# RAM_Board_Deux.net
KiCad netlist of a schematic drawn in EAGLE
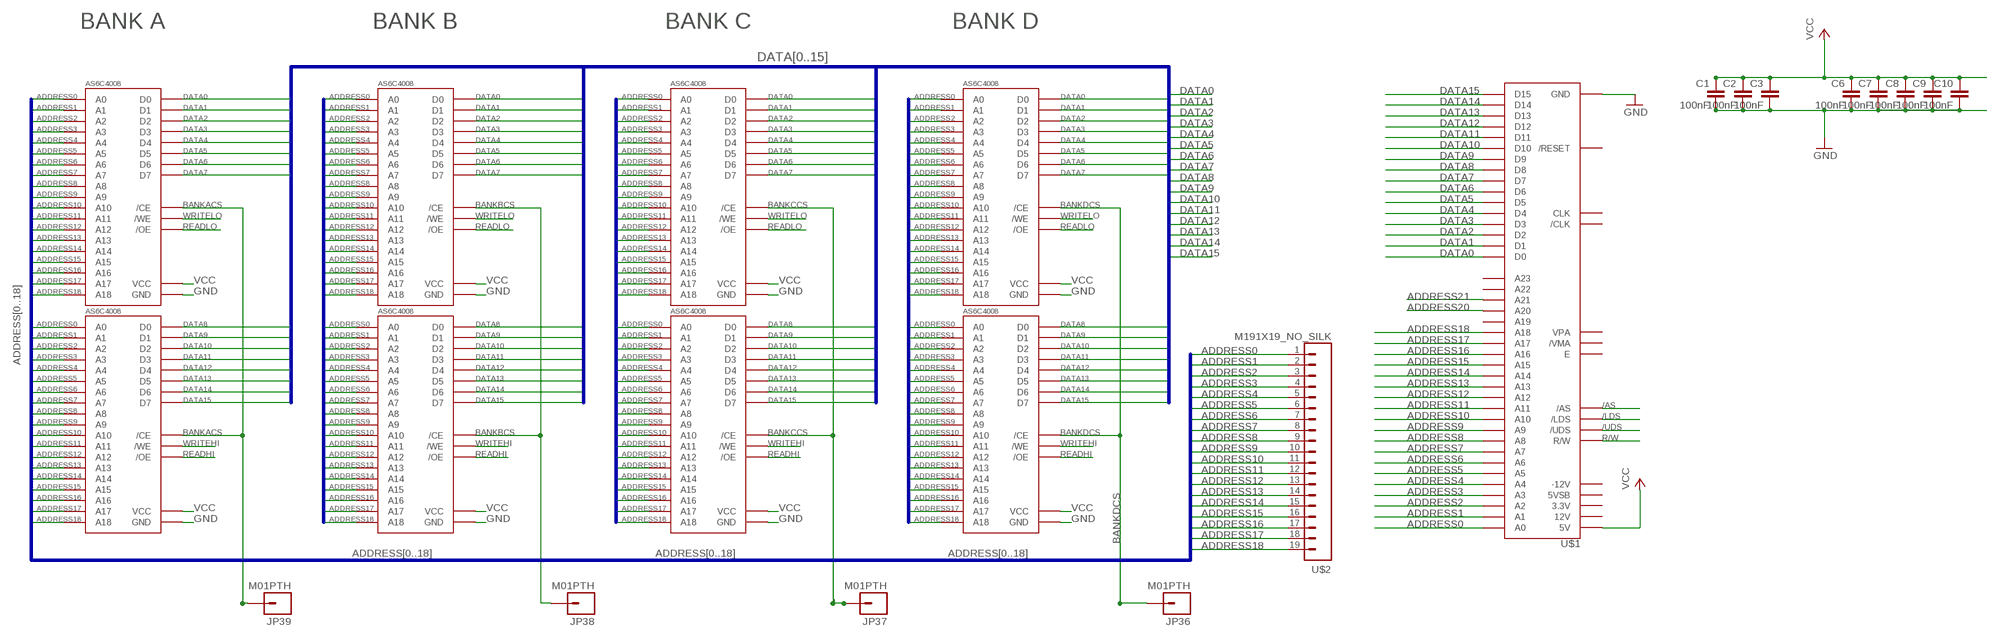
[diagram p0: schematic, sheet 1]

(export (version "E")
  (design (tool "Eeschema 10.0.6"))
  (components
    (comp (ref "C1")
      (value "100nF")
      (footprint "eagle-import:CAP-PTH-SMALL")
      (libsource (lib "eagle-import") (part "CAPPTH"))
    )
    (comp (ref "C2")
      (value "100nF")
      (footprint "eagle-import:CAP-PTH-SMALL")
      (libsource (lib "eagle-import") (part "CAPPTH"))
    )
    (comp (ref "C3")
      (value "100nF")
      (footprint "eagle-import:CAP-PTH-SMALL")
      (libsource (lib "eagle-import") (part "CAPPTH"))
    )
    (comp (ref "C6")
      (value "100nF")
      (footprint "eagle-import:CAP-PTH-SMALL")
      (libsource (lib "eagle-import") (part "CAPPTH"))
    )
    (comp (ref "C7")
      (value "100nF")
      (footprint "eagle-import:CAP-PTH-SMALL")
      (libsource (lib "eagle-import") (part "CAPPTH"))
    )
    (comp (ref "C8")
      (value "100nF")
      (footprint "eagle-import:CAP-PTH-SMALL")
      (libsource (lib "eagle-import") (part "CAPPTH"))
    )
    (comp (ref "C9")
      (value "100nF")
      (footprint "eagle-import:CAP-PTH-SMALL")
      (libsource (lib "eagle-import") (part "CAPPTH"))
    )
    (comp (ref "C10")
      (value "100nF")
      (footprint "eagle-import:CAP-PTH-SMALL")
      (libsource (lib "eagle-import") (part "CAPPTH"))
    )
    (comp (ref "JP36")
      (value "M01PTH")
      (footprint "eagle-import:1X01")
      (libsource (lib "eagle-import") (part "M01PTH"))
    )
    (comp (ref "JP37")
      (value "M01PTH")
      (footprint "eagle-import:1X01")
      (libsource (lib "eagle-import") (part "M01PTH"))
    )
    (comp (ref "JP38")
      (value "M01PTH")
      (footprint "eagle-import:1X01")
      (libsource (lib "eagle-import") (part "M01PTH"))
    )
    (comp (ref "JP39")
      (value "M01PTH")
      (footprint "eagle-import:1X01")
      (libsource (lib "eagle-import") (part "M01PTH"))
    )
    (comp (ref "U$1")
      (value "BLANKBOARD")
      (footprint "eagle-import:BLANKBOARD")
      (libsource (lib "eagle-import") (part "BLANKBOARD"))
    )
    (comp (ref "U$2")
      (value "M191X19_NO_SILK")
      (footprint "eagle-import:1X19_NO_SILK")
      (libsource (lib "eagle-import") (part "M191X19_NO_SILK"))
    )
    (comp (ref "U1")
      (value "AS6C4008")
      (footprint "eagle-import:DIL32")
      (libsource (lib "eagle-import") (part "AS6C4008"))
    )
    (comp (ref "U2")
      (value "AS6C4008")
      (footprint "eagle-import:DIL32")
      (libsource (lib "eagle-import") (part "AS6C4008"))
    )
    (comp (ref "U3")
      (value "AS6C4008")
      (footprint "eagle-import:DIL32")
      (libsource (lib "eagle-import") (part "AS6C4008"))
    )
    (comp (ref "U4")
      (value "AS6C4008")
      (footprint "eagle-import:DIL32")
      (libsource (lib "eagle-import") (part "AS6C4008"))
    )
    (comp (ref "U5")
      (value "AS6C4008")
      (footprint "eagle-import:DIL32")
      (libsource (lib "eagle-import") (part "AS6C4008"))
    )
    (comp (ref "U6")
      (value "AS6C4008")
      (footprint "eagle-import:DIL32")
      (libsource (lib "eagle-import") (part "AS6C4008"))
    )
    (comp (ref "U7")
      (value "AS6C4008")
      (footprint "eagle-import:DIL32")
      (libsource (lib "eagle-import") (part "AS6C4008"))
    )
    (comp (ref "U8")
      (value "AS6C4008")
      (footprint "eagle-import:DIL32")
      (libsource (lib "eagle-import") (part "AS6C4008"))
    )
  )
  (nets
    (net (code "3") (name "ADDRESS0") (class "Default")
      (node (ref "U$1") (pin "A0") (pinfunction "A0_A0") (pintype "bidirectional"))
      (node (ref "U$2") (pin "1") (pinfunction "1_1") (pintype "passive"))
      (node (ref "U1") (pin "12") (pinfunction "A0_12") (pintype "input"))
      (node (ref "U2") (pin "12") (pinfunction "A0_12") (pintype "input"))
      (node (ref "U3") (pin "12") (pinfunction "A0_12") (pintype "input"))
      (node (ref "U4") (pin "12") (pinfunction "A0_12") (pintype "input"))
      (node (ref "U5") (pin "12") (pinfunction "A0_12") (pintype "input"))
      (node (ref "U6") (pin "12") (pinfunction "A0_12") (pintype "input"))
      (node (ref "U7") (pin "12") (pinfunction "A0_12") (pintype "input"))
      (node (ref "U8") (pin "12") (pinfunction "A0_12") (pintype "input"))
    )
    (net (code "4") (name "ADDRESS1") (class "Default")
      (node (ref "U$1") (pin "A1") (pinfunction "A1_A1") (pintype "bidirectional"))
      (node (ref "U$2") (pin "2") (pinfunction "2_2") (pintype "passive"))
      (node (ref "U1") (pin "11") (pinfunction "A1_11") (pintype "input"))
      (node (ref "U2") (pin "11") (pinfunction "A1_11") (pintype "input"))
      (node (ref "U3") (pin "11") (pinfunction "A1_11") (pintype "input"))
      (node (ref "U4") (pin "11") (pinfunction "A1_11") (pintype "input"))
      (node (ref "U5") (pin "11") (pinfunction "A1_11") (pintype "input"))
      (node (ref "U6") (pin "11") (pinfunction "A1_11") (pintype "input"))
      (node (ref "U7") (pin "11") (pinfunction "A1_11") (pintype "input"))
      (node (ref "U8") (pin "11") (pinfunction "A1_11") (pintype "input"))
    )
    (net (code "5") (name "ADDRESS2") (class "Default")
      (node (ref "U$1") (pin "A2") (pinfunction "A2_A2") (pintype "bidirectional"))
      (node (ref "U$2") (pin "3") (pinfunction "3_3") (pintype "passive"))
      (node (ref "U1") (pin "10") (pinfunction "A2_10") (pintype "input"))
      (node (ref "U2") (pin "10") (pinfunction "A2_10") (pintype "input"))
      (node (ref "U3") (pin "10") (pinfunction "A2_10") (pintype "input"))
      (node (ref "U4") (pin "10") (pinfunction "A2_10") (pintype "input"))
      (node (ref "U5") (pin "10") (pinfunction "A2_10") (pintype "input"))
      (node (ref "U6") (pin "10") (pinfunction "A2_10") (pintype "input"))
      (node (ref "U7") (pin "10") (pinfunction "A2_10") (pintype "input"))
      (node (ref "U8") (pin "10") (pinfunction "A2_10") (pintype "input"))
    )
    (net (code "6") (name "ADDRESS3") (class "Default")
      (node (ref "U$1") (pin "A3") (pinfunction "A3_A3") (pintype "bidirectional"))
      (node (ref "U$2") (pin "4") (pinfunction "4_4") (pintype "passive"))
      (node (ref "U1") (pin "9") (pinfunction "A3_9") (pintype "input"))
      (node (ref "U2") (pin "9") (pinfunction "A3_9") (pintype "input"))
      (node (ref "U3") (pin "9") (pinfunction "A3_9") (pintype "input"))
      (node (ref "U4") (pin "9") (pinfunction "A3_9") (pintype "input"))
      (node (ref "U5") (pin "9") (pinfunction "A3_9") (pintype "input"))
      (node (ref "U6") (pin "9") (pinfunction "A3_9") (pintype "input"))
      (node (ref "U7") (pin "9") (pinfunction "A3_9") (pintype "input"))
      (node (ref "U8") (pin "9") (pinfunction "A3_9") (pintype "input"))
    )
    (net (code "7") (name "ADDRESS4") (class "Default")
      (node (ref "U$1") (pin "A4") (pinfunction "A4_A4") (pintype "bidirectional"))
      (node (ref "U$2") (pin "5") (pinfunction "5_5") (pintype "passive"))
      (node (ref "U1") (pin "8") (pinfunction "A4_8") (pintype "input"))
      (node (ref "U2") (pin "8") (pinfunction "A4_8") (pintype "input"))
      (node (ref "U3") (pin "8") (pinfunction "A4_8") (pintype "input"))
      (node (ref "U4") (pin "8") (pinfunction "A4_8") (pintype "input"))
      (node (ref "U5") (pin "8") (pinfunction "A4_8") (pintype "input"))
      (node (ref "U6") (pin "8") (pinfunction "A4_8") (pintype "input"))
      (node (ref "U7") (pin "8") (pinfunction "A4_8") (pintype "input"))
      (node (ref "U8") (pin "8") (pinfunction "A4_8") (pintype "input"))
    )
    (net (code "8") (name "ADDRESS5") (class "Default")
      (node (ref "U$1") (pin "A5") (pinfunction "A5_A5") (pintype "bidirectional"))
      (node (ref "U$2") (pin "6") (pinfunction "6_6") (pintype "passive"))
      (node (ref "U1") (pin "7") (pinfunction "A5_7") (pintype "input"))
      (node (ref "U2") (pin "7") (pinfunction "A5_7") (pintype "input"))
      (node (ref "U3") (pin "7") (pinfunction "A5_7") (pintype "input"))
      (node (ref "U4") (pin "7") (pinfunction "A5_7") (pintype "input"))
      (node (ref "U5") (pin "7") (pinfunction "A5_7") (pintype "input"))
      (node (ref "U6") (pin "7") (pinfunction "A5_7") (pintype "input"))
      (node (ref "U7") (pin "7") (pinfunction "A5_7") (pintype "input"))
      (node (ref "U8") (pin "7") (pinfunction "A5_7") (pintype "input"))
    )
    (net (code "9") (name "ADDRESS6") (class "Default")
      (node (ref "U$1") (pin "A6") (pinfunction "A6_A6") (pintype "bidirectional"))
      (node (ref "U$2") (pin "7") (pinfunction "7_7") (pintype "passive"))
      (node (ref "U1") (pin "6") (pinfunction "A6_6") (pintype "input"))
      (node (ref "U2") (pin "6") (pinfunction "A6_6") (pintype "input"))
      (node (ref "U3") (pin "6") (pinfunction "A6_6") (pintype "input"))
      (node (ref "U4") (pin "6") (pinfunction "A6_6") (pintype "input"))
      (node (ref "U5") (pin "6") (pinfunction "A6_6") (pintype "input"))
      (node (ref "U6") (pin "6") (pinfunction "A6_6") (pintype "input"))
      (node (ref "U7") (pin "6") (pinfunction "A6_6") (pintype "input"))
      (node (ref "U8") (pin "6") (pinfunction "A6_6") (pintype "input"))
    )
    (net (code "10") (name "ADDRESS7") (class "Default")
      (node (ref "U$1") (pin "A7") (pinfunction "A7_A7") (pintype "bidirectional"))
      (node (ref "U$2") (pin "8") (pinfunction "8_8") (pintype "passive"))
      (node (ref "U1") (pin "5") (pinfunction "A7_5") (pintype "input"))
      (node (ref "U2") (pin "5") (pinfunction "A7_5") (pintype "input"))
      (node (ref "U3") (pin "5") (pinfunction "A7_5") (pintype "input"))
      (node (ref "U4") (pin "5") (pinfunction "A7_5") (pintype "input"))
      (node (ref "U5") (pin "5") (pinfunction "A7_5") (pintype "input"))
      (node (ref "U6") (pin "5") (pinfunction "A7_5") (pintype "input"))
      (node (ref "U7") (pin "5") (pinfunction "A7_5") (pintype "input"))
      (node (ref "U8") (pin "5") (pinfunction "A7_5") (pintype "input"))
    )
    (net (code "11") (name "ADDRESS8") (class "Default")
      (node (ref "U$1") (pin "A8") (pinfunction "A8_A8") (pintype "bidirectional"))
      (node (ref "U$2") (pin "9") (pinfunction "9_9") (pintype "passive"))
      (node (ref "U1") (pin "27") (pinfunction "A8_27") (pintype "input"))
      (node (ref "U2") (pin "27") (pinfunction "A8_27") (pintype "input"))
      (node (ref "U3") (pin "27") (pinfunction "A8_27") (pintype "input"))
      (node (ref "U4") (pin "27") (pinfunction "A8_27") (pintype "input"))
      (node (ref "U5") (pin "27") (pinfunction "A8_27") (pintype "input"))
      (node (ref "U6") (pin "27") (pinfunction "A8_27") (pintype "input"))
      (node (ref "U7") (pin "27") (pinfunction "A8_27") (pintype "input"))
      (node (ref "U8") (pin "27") (pinfunction "A8_27") (pintype "input"))
    )
    (net (code "12") (name "ADDRESS9") (class "Default")
      (node (ref "U$1") (pin "A9") (pinfunction "A9_A9") (pintype "bidirectional"))
      (node (ref "U$2") (pin "10") (pinfunction "10_10") (pintype "passive"))
      (node (ref "U1") (pin "26") (pinfunction "A9_26") (pintype "input"))
      (node (ref "U2") (pin "26") (pinfunction "A9_26") (pintype "input"))
      (node (ref "U3") (pin "26") (pinfunction "A9_26") (pintype "input"))
      (node (ref "U4") (pin "26") (pinfunction "A9_26") (pintype "input"))
      (node (ref "U5") (pin "26") (pinfunction "A9_26") (pintype "input"))
      (node (ref "U6") (pin "26") (pinfunction "A9_26") (pintype "input"))
      (node (ref "U7") (pin "26") (pinfunction "A9_26") (pintype "input"))
      (node (ref "U8") (pin "26") (pinfunction "A9_26") (pintype "input"))
    )
    (net (code "13") (name "ADDRESS10") (class "Default")
      (node (ref "U$1") (pin "A10") (pinfunction "A10_A10") (pintype "bidirectional"))
      (node (ref "U$2") (pin "11") (pinfunction "11_11") (pintype "passive"))
      (node (ref "U1") (pin "23") (pinfunction "A10_23") (pintype "input"))
      (node (ref "U2") (pin "23") (pinfunction "A10_23") (pintype "input"))
      (node (ref "U3") (pin "23") (pinfunction "A10_23") (pintype "input"))
      (node (ref "U4") (pin "23") (pinfunction "A10_23") (pintype "input"))
      (node (ref "U5") (pin "23") (pinfunction "A10_23") (pintype "input"))
      (node (ref "U6") (pin "23") (pinfunction "A10_23") (pintype "input"))
      (node (ref "U7") (pin "23") (pinfunction "A10_23") (pintype "input"))
      (node (ref "U8") (pin "23") (pinfunction "A10_23") (pintype "input"))
    )
    (net (code "14") (name "ADDRESS11") (class "Default")
      (node (ref "U$1") (pin "A11") (pinfunction "A11_A11") (pintype "bidirectional"))
      (node (ref "U$2") (pin "12") (pinfunction "12_12") (pintype "passive"))
      (node (ref "U1") (pin "25") (pinfunction "A11_25") (pintype "input"))
      (node (ref "U2") (pin "25") (pinfunction "A11_25") (pintype "input"))
      (node (ref "U3") (pin "25") (pinfunction "A11_25") (pintype "input"))
      (node (ref "U4") (pin "25") (pinfunction "A11_25") (pintype "input"))
      (node (ref "U5") (pin "25") (pinfunction "A11_25") (pintype "input"))
      (node (ref "U6") (pin "25") (pinfunction "A11_25") (pintype "input"))
      (node (ref "U7") (pin "25") (pinfunction "A11_25") (pintype "input"))
      (node (ref "U8") (pin "25") (pinfunction "A11_25") (pintype "input"))
    )
    (net (code "15") (name "ADDRESS12") (class "Default")
      (node (ref "U$1") (pin "A12") (pinfunction "A12_A12") (pintype "bidirectional"))
      (node (ref "U$2") (pin "13") (pinfunction "13_13") (pintype "passive"))
      (node (ref "U1") (pin "4") (pinfunction "A12_4") (pintype "input"))
      (node (ref "U2") (pin "4") (pinfunction "A12_4") (pintype "input"))
      (node (ref "U3") (pin "4") (pinfunction "A12_4") (pintype "input"))
      (node (ref "U4") (pin "4") (pinfunction "A12_4") (pintype "input"))
      (node (ref "U5") (pin "4") (pinfunction "A12_4") (pintype "input"))
      (node (ref "U6") (pin "4") (pinfunction "A12_4") (pintype "input"))
      (node (ref "U7") (pin "4") (pinfunction "A12_4") (pintype "input"))
      (node (ref "U8") (pin "4") (pinfunction "A12_4") (pintype "input"))
    )
    (net (code "16") (name "ADDRESS13") (class "Default")
      (node (ref "U$1") (pin "A13") (pinfunction "A13_A13") (pintype "bidirectional"))
      (node (ref "U$2") (pin "14") (pinfunction "14_14") (pintype "passive"))
      (node (ref "U1") (pin "28") (pinfunction "A13_28") (pintype "input"))
      (node (ref "U2") (pin "28") (pinfunction "A13_28") (pintype "input"))
      (node (ref "U3") (pin "28") (pinfunction "A13_28") (pintype "input"))
      (node (ref "U4") (pin "28") (pinfunction "A13_28") (pintype "input"))
      (node (ref "U5") (pin "28") (pinfunction "A13_28") (pintype "input"))
      (node (ref "U6") (pin "28") (pinfunction "A13_28") (pintype "input"))
      (node (ref "U7") (pin "28") (pinfunction "A13_28") (pintype "input"))
      (node (ref "U8") (pin "28") (pinfunction "A13_28") (pintype "input"))
    )
    (net (code "17") (name "ADDRESS14") (class "Default")
      (node (ref "U$1") (pin "A14") (pinfunction "A14_A14") (pintype "bidirectional"))
      (node (ref "U$2") (pin "15") (pinfunction "15_15") (pintype "passive"))
      (node (ref "U1") (pin "3") (pinfunction "A14_3") (pintype "input"))
      (node (ref "U2") (pin "3") (pinfunction "A14_3") (pintype "input"))
      (node (ref "U3") (pin "3") (pinfunction "A14_3") (pintype "input"))
      (node (ref "U4") (pin "3") (pinfunction "A14_3") (pintype "input"))
      (node (ref "U5") (pin "3") (pinfunction "A14_3") (pintype "input"))
      (node (ref "U6") (pin "3") (pinfunction "A14_3") (pintype "input"))
      (node (ref "U7") (pin "3") (pinfunction "A14_3") (pintype "input"))
      (node (ref "U8") (pin "3") (pinfunction "A14_3") (pintype "input"))
    )
    (net (code "18") (name "ADDRESS15") (class "Default")
      (node (ref "U$1") (pin "A15") (pinfunction "A15_A15") (pintype "bidirectional"))
      (node (ref "U$2") (pin "16") (pinfunction "16_16") (pintype "passive"))
      (node (ref "U1") (pin "31") (pinfunction "A15_31") (pintype "input"))
      (node (ref "U2") (pin "31") (pinfunction "A15_31") (pintype "input"))
      (node (ref "U3") (pin "31") (pinfunction "A15_31") (pintype "input"))
      (node (ref "U4") (pin "31") (pinfunction "A15_31") (pintype "input"))
      (node (ref "U5") (pin "31") (pinfunction "A15_31") (pintype "input"))
      (node (ref "U6") (pin "31") (pinfunction "A15_31") (pintype "input"))
      (node (ref "U7") (pin "31") (pinfunction "A15_31") (pintype "input"))
      (node (ref "U8") (pin "31") (pinfunction "A15_31") (pintype "input"))
    )
    (net (code "19") (name "ADDRESS16") (class "Default")
      (node (ref "U$1") (pin "A16") (pinfunction "A16_A16") (pintype "bidirectional"))
      (node (ref "U$2") (pin "17") (pinfunction "17_17") (pintype "passive"))
      (node (ref "U1") (pin "2") (pinfunction "A16_2") (pintype "input"))
      (node (ref "U2") (pin "2") (pinfunction "A16_2") (pintype "input"))
      (node (ref "U3") (pin "2") (pinfunction "A16_2") (pintype "input"))
      (node (ref "U4") (pin "2") (pinfunction "A16_2") (pintype "input"))
      (node (ref "U5") (pin "2") (pinfunction "A16_2") (pintype "input"))
      (node (ref "U6") (pin "2") (pinfunction "A16_2") (pintype "input"))
      (node (ref "U7") (pin "2") (pinfunction "A16_2") (pintype "input"))
      (node (ref "U8") (pin "2") (pinfunction "A16_2") (pintype "input"))
    )
    (net (code "20") (name "ADDRESS17") (class "Default")
      (node (ref "U$1") (pin "A17") (pinfunction "A17_A17") (pintype "bidirectional"))
      (node (ref "U$2") (pin "18") (pinfunction "18_18") (pintype "passive"))
      (node (ref "U1") (pin "30") (pinfunction "A17_30") (pintype "input"))
      (node (ref "U2") (pin "30") (pinfunction "A17_30") (pintype "input"))
      (node (ref "U3") (pin "30") (pinfunction "A17_30") (pintype "input"))
      (node (ref "U4") (pin "30") (pinfunction "A17_30") (pintype "input"))
      (node (ref "U5") (pin "30") (pinfunction "A17_30") (pintype "input"))
      (node (ref "U6") (pin "30") (pinfunction "A17_30") (pintype "input"))
      (node (ref "U7") (pin "30") (pinfunction "A17_30") (pintype "input"))
      (node (ref "U8") (pin "30") (pinfunction "A17_30") (pintype "input"))
    )
    (net (code "21") (name "ADDRESS18") (class "Default")
      (node (ref "U$1") (pin "A18") (pinfunction "A18_A18") (pintype "bidirectional"))
      (node (ref "U$2") (pin "19") (pinfunction "19_19") (pintype "passive"))
      (node (ref "U1") (pin "1") (pinfunction "A18_1") (pintype "input"))
      (node (ref "U2") (pin "1") (pinfunction "A18_1") (pintype "input"))
      (node (ref "U3") (pin "1") (pinfunction "A18_1") (pintype "input"))
      (node (ref "U4") (pin "1") (pinfunction "A18_1") (pintype "input"))
      (node (ref "U5") (pin "1") (pinfunction "A18_1") (pintype "input"))
      (node (ref "U6") (pin "1") (pinfunction "A18_1") (pintype "input"))
      (node (ref "U7") (pin "1") (pinfunction "A18_1") (pintype "input"))
      (node (ref "U8") (pin "1") (pinfunction "A18_1") (pintype "input"))
    )
    (net (code "22") (name "ADDRESS20") (class "Default")
      (node (ref "U$1") (pin "A20") (pinfunction "A20_A20") (pintype "bidirectional"))
    )
    (net (code "23") (name "ADDRESS21") (class "Default")
      (node (ref "U$1") (pin "A21") (pinfunction "A21_A21") (pintype "bidirectional"))
    )
    (net (code "24") (name "BANKACS") (class "Default")
      (node (ref "JP39") (pin "1") (pinfunction "1_1") (pintype "passive"))
      (node (ref "U1") (pin "22") (pinfunction "/CE_22") (pintype "input"))
      (node (ref "U2") (pin "22") (pinfunction "/CE_22") (pintype "input"))
    )
    (net (code "25") (name "BANKBCS") (class "Default")
      (node (ref "JP38") (pin "1") (pinfunction "1_1") (pintype "passive"))
      (node (ref "U3") (pin "22") (pinfunction "/CE_22") (pintype "input"))
      (node (ref "U4") (pin "22") (pinfunction "/CE_22") (pintype "input"))
    )
    (net (code "26") (name "BANKCCS") (class "Default")
      (node (ref "JP37") (pin "1") (pinfunction "1_1") (pintype "passive"))
      (node (ref "U5") (pin "22") (pinfunction "/CE_22") (pintype "input"))
      (node (ref "U6") (pin "22") (pinfunction "/CE_22") (pintype "input"))
    )
    (net (code "27") (name "BANKDCS") (class "Default")
      (node (ref "JP36") (pin "1") (pinfunction "1_1") (pintype "passive"))
      (node (ref "U7") (pin "22") (pinfunction "/CE_22") (pintype "input"))
      (node (ref "U8") (pin "22") (pinfunction "/CE_22") (pintype "input"))
    )
    (net (code "28") (name "DATA0") (class "Default")
      (node (ref "U$1") (pin "D0") (pinfunction "D0_D0") (pintype "bidirectional"))
      (node (ref "U2") (pin "13") (pinfunction "D0_13") (pintype "input"))
      (node (ref "U4") (pin "13") (pinfunction "D0_13") (pintype "input"))
      (node (ref "U6") (pin "13") (pinfunction "D0_13") (pintype "input"))
      (node (ref "U8") (pin "13") (pinfunction "D0_13") (pintype "input"))
    )
    (net (code "29") (name "DATA1") (class "Default")
      (node (ref "U$1") (pin "D1") (pinfunction "D1_D1") (pintype "bidirectional"))
      (node (ref "U2") (pin "14") (pinfunction "D1_14") (pintype "input"))
      (node (ref "U4") (pin "14") (pinfunction "D1_14") (pintype "input"))
      (node (ref "U6") (pin "14") (pinfunction "D1_14") (pintype "input"))
      (node (ref "U8") (pin "14") (pinfunction "D1_14") (pintype "input"))
    )
    (net (code "30") (name "DATA2") (class "Default")
      (node (ref "U$1") (pin "D2") (pinfunction "D2_D2") (pintype "bidirectional"))
      (node (ref "U2") (pin "15") (pinfunction "D2_15") (pintype "input"))
      (node (ref "U4") (pin "15") (pinfunction "D2_15") (pintype "input"))
      (node (ref "U6") (pin "15") (pinfunction "D2_15") (pintype "input"))
      (node (ref "U8") (pin "15") (pinfunction "D2_15") (pintype "input"))
    )
    (net (code "31") (name "DATA3") (class "Default")
      (node (ref "U$1") (pin "D3") (pinfunction "D3_D3") (pintype "bidirectional"))
      (node (ref "U2") (pin "17") (pinfunction "D3_17") (pintype "input"))
      (node (ref "U4") (pin "17") (pinfunction "D3_17") (pintype "input"))
      (node (ref "U6") (pin "17") (pinfunction "D3_17") (pintype "input"))
      (node (ref "U8") (pin "17") (pinfunction "D3_17") (pintype "input"))
    )
    (net (code "32") (name "DATA4") (class "Default")
      (node (ref "U$1") (pin "D4") (pinfunction "D4_D4") (pintype "bidirectional"))
      (node (ref "U2") (pin "18") (pinfunction "D4_18") (pintype "input"))
      (node (ref "U4") (pin "18") (pinfunction "D4_18") (pintype "input"))
      (node (ref "U6") (pin "18") (pinfunction "D4_18") (pintype "input"))
      (node (ref "U8") (pin "18") (pinfunction "D4_18") (pintype "input"))
    )
    (net (code "33") (name "DATA5") (class "Default")
      (node (ref "U$1") (pin "D5") (pinfunction "D5_D5") (pintype "bidirectional"))
      (node (ref "U2") (pin "19") (pinfunction "D5_19") (pintype "input"))
      (node (ref "U4") (pin "19") (pinfunction "D5_19") (pintype "input"))
      (node (ref "U6") (pin "19") (pinfunction "D5_19") (pintype "input"))
      (node (ref "U8") (pin "19") (pinfunction "D5_19") (pintype "input"))
    )
    (net (code "34") (name "DATA6") (class "Default")
      (node (ref "U$1") (pin "D6") (pinfunction "D6_D6") (pintype "bidirectional"))
      (node (ref "U2") (pin "20") (pinfunction "D6_20") (pintype "input"))
      (node (ref "U4") (pin "20") (pinfunction "D6_20") (pintype "input"))
      (node (ref "U6") (pin "20") (pinfunction "D6_20") (pintype "input"))
      (node (ref "U8") (pin "20") (pinfunction "D6_20") (pintype "input"))
    )
    (net (code "35") (name "DATA7") (class "Default")
      (node (ref "U$1") (pin "D7") (pinfunction "D7_D7") (pintype "bidirectional"))
      (node (ref "U2") (pin "21") (pinfunction "D7_21") (pintype "input"))
      (node (ref "U4") (pin "21") (pinfunction "D7_21") (pintype "input"))
      (node (ref "U6") (pin "21") (pinfunction "D7_21") (pintype "input"))
      (node (ref "U8") (pin "21") (pinfunction "D7_21") (pintype "input"))
    )
    (net (code "36") (name "DATA8") (class "Default")
      (node (ref "U$1") (pin "D8") (pinfunction "D8_D8") (pintype "bidirectional"))
      (node (ref "U1") (pin "13") (pinfunction "D0_13") (pintype "input"))
      (node (ref "U3") (pin "13") (pinfunction "D0_13") (pintype "input"))
      (node (ref "U5") (pin "13") (pinfunction "D0_13") (pintype "input"))
      (node (ref "U7") (pin "13") (pinfunction "D0_13") (pintype "input"))
    )
    (net (code "37") (name "DATA9") (class "Default")
      (node (ref "U$1") (pin "D9") (pinfunction "D9_D9") (pintype "bidirectional"))
      (node (ref "U1") (pin "14") (pinfunction "D1_14") (pintype "input"))
      (node (ref "U3") (pin "14") (pinfunction "D1_14") (pintype "input"))
      (node (ref "U5") (pin "14") (pinfunction "D1_14") (pintype "input"))
      (node (ref "U7") (pin "14") (pinfunction "D1_14") (pintype "input"))
    )
    (net (code "38") (name "DATA10") (class "Default")
      (node (ref "U$1") (pin "D10") (pinfunction "D10_D10") (pintype "bidirectional"))
      (node (ref "U1") (pin "15") (pinfunction "D2_15") (pintype "input"))
      (node (ref "U3") (pin "15") (pinfunction "D2_15") (pintype "input"))
      (node (ref "U5") (pin "15") (pinfunction "D2_15") (pintype "input"))
      (node (ref "U7") (pin "15") (pinfunction "D2_15") (pintype "input"))
    )
    (net (code "39") (name "DATA11") (class "Default")
      (node (ref "U$1") (pin "D11") (pinfunction "D11_D11") (pintype "bidirectional"))
      (node (ref "U1") (pin "17") (pinfunction "D3_17") (pintype "input"))
      (node (ref "U3") (pin "17") (pinfunction "D3_17") (pintype "input"))
      (node (ref "U5") (pin "17") (pinfunction "D3_17") (pintype "input"))
      (node (ref "U7") (pin "17") (pinfunction "D3_17") (pintype "input"))
    )
    (net (code "40") (name "DATA12") (class "Default")
      (node (ref "U$1") (pin "D12") (pinfunction "D12_D12") (pintype "bidirectional"))
      (node (ref "U1") (pin "18") (pinfunction "D4_18") (pintype "input"))
      (node (ref "U3") (pin "18") (pinfunction "D4_18") (pintype "input"))
      (node (ref "U5") (pin "18") (pinfunction "D4_18") (pintype "input"))
      (node (ref "U7") (pin "18") (pinfunction "D4_18") (pintype "input"))
    )
    (net (code "41") (name "DATA13") (class "Default")
      (node (ref "U$1") (pin "D13") (pinfunction "D13_D13") (pintype "bidirectional"))
      (node (ref "U1") (pin "19") (pinfunction "D5_19") (pintype "input"))
      (node (ref "U3") (pin "19") (pinfunction "D5_19") (pintype "input"))
      (node (ref "U5") (pin "19") (pinfunction "D5_19") (pintype "input"))
      (node (ref "U7") (pin "19") (pinfunction "D5_19") (pintype "input"))
    )
    (net (code "42") (name "DATA14") (class "Default")
      (node (ref "U$1") (pin "D14") (pinfunction "D14_D14") (pintype "bidirectional"))
      (node (ref "U1") (pin "20") (pinfunction "D6_20") (pintype "input"))
      (node (ref "U3") (pin "20") (pinfunction "D6_20") (pintype "input"))
      (node (ref "U5") (pin "20") (pinfunction "D6_20") (pintype "input"))
      (node (ref "U7") (pin "20") (pinfunction "D6_20") (pintype "input"))
    )
    (net (code "43") (name "DATA15") (class "Default")
      (node (ref "U$1") (pin "D15") (pinfunction "D15_D15") (pintype "bidirectional"))
      (node (ref "U1") (pin "21") (pinfunction "D7_21") (pintype "input"))
      (node (ref "U3") (pin "21") (pinfunction "D7_21") (pintype "input"))
      (node (ref "U5") (pin "21") (pinfunction "D7_21") (pintype "input"))
      (node (ref "U7") (pin "21") (pinfunction "D7_21") (pintype "input"))
    )
    (net (code "44") (name "GND") (class "Default")
      (node (ref "C1") (pin "2") (pinfunction "2_2") (pintype "passive"))
      (node (ref "C10") (pin "2") (pinfunction "2_2") (pintype "passive"))
      (node (ref "C2") (pin "2") (pinfunction "2_2") (pintype "passive"))
      (node (ref "C3") (pin "2") (pinfunction "2_2") (pintype "passive"))
      (node (ref "C6") (pin "2") (pinfunction "2_2") (pintype "passive"))
      (node (ref "C7") (pin "2") (pinfunction "2_2") (pintype "passive"))
      (node (ref "C8") (pin "2") (pinfunction "2_2") (pintype "passive"))
      (node (ref "C9") (pin "2") (pinfunction "2_2") (pintype "passive"))
      (node (ref "U$1") (pin "GND") (pinfunction "GND_GND") (pintype "bidirectional"))
      (node (ref "U1") (pin "16") (pinfunction "GND_16") (pintype "input"))
      (node (ref "U2") (pin "16") (pinfunction "GND_16") (pintype "input"))
      (node (ref "U3") (pin "16") (pinfunction "GND_16") (pintype "input"))
      (node (ref "U4") (pin "16") (pinfunction "GND_16") (pintype "input"))
      (node (ref "U5") (pin "16") (pinfunction "GND_16") (pintype "input"))
      (node (ref "U6") (pin "16") (pinfunction "GND_16") (pintype "input"))
      (node (ref "U7") (pin "16") (pinfunction "GND_16") (pintype "input"))
      (node (ref "U8") (pin "16") (pinfunction "GND_16") (pintype "input"))
    )
    (net (code "45") (name "READHI") (class "Default")
      (node (ref "U1") (pin "24") (pinfunction "/OE_24") (pintype "input"))
      (node (ref "U3") (pin "24") (pinfunction "/OE_24") (pintype "input"))
      (node (ref "U5") (pin "24") (pinfunction "/OE_24") (pintype "input"))
      (node (ref "U7") (pin "24") (pinfunction "/OE_24") (pintype "input"))
    )
    (net (code "46") (name "READLO") (class "Default")
      (node (ref "U2") (pin "24") (pinfunction "/OE_24") (pintype "input"))
      (node (ref "U4") (pin "24") (pinfunction "/OE_24") (pintype "input"))
      (node (ref "U6") (pin "24") (pinfunction "/OE_24") (pintype "input"))
      (node (ref "U8") (pin "24") (pinfunction "/OE_24") (pintype "input"))
    )
    (net (code "47") (name "R{slash}W") (class "Default")
      (node (ref "U$1") (pin "R/W") (pinfunction "R/W_R/W") (pintype "bidirectional"))
    )
    (net (code "48") (name "VCC") (class "Default")
      (node (ref "C1") (pin "1") (pinfunction "1_1") (pintype "passive"))
      (node (ref "C10") (pin "1") (pinfunction "1_1") (pintype "passive"))
      (node (ref "C2") (pin "1") (pinfunction "1_1") (pintype "passive"))
      (node (ref "C3") (pin "1") (pinfunction "1_1") (pintype "passive"))
      (node (ref "C6") (pin "1") (pinfunction "1_1") (pintype "passive"))
      (node (ref "C7") (pin "1") (pinfunction "1_1") (pintype "passive"))
      (node (ref "C8") (pin "1") (pinfunction "1_1") (pintype "passive"))
      (node (ref "C9") (pin "1") (pinfunction "1_1") (pintype "passive"))
      (node (ref "U$1") (pin "5V") (pinfunction "5V_5V") (pintype "bidirectional"))
      (node (ref "U1") (pin "32") (pinfunction "VCC_32") (pintype "input"))
      (node (ref "U2") (pin "32") (pinfunction "VCC_32") (pintype "input"))
      (node (ref "U3") (pin "32") (pinfunction "VCC_32") (pintype "input"))
      (node (ref "U4") (pin "32") (pinfunction "VCC_32") (pintype "input"))
      (node (ref "U5") (pin "32") (pinfunction "VCC_32") (pintype "input"))
      (node (ref "U6") (pin "32") (pinfunction "VCC_32") (pintype "input"))
      (node (ref "U7") (pin "32") (pinfunction "VCC_32") (pintype "input"))
      (node (ref "U8") (pin "32") (pinfunction "VCC_32") (pintype "input"))
    )
    (net (code "49") (name "WRITEHI") (class "Default")
      (node (ref "U1") (pin "29") (pinfunction "/WE_29") (pintype "input"))
      (node (ref "U3") (pin "29") (pinfunction "/WE_29") (pintype "input"))
      (node (ref "U5") (pin "29") (pinfunction "/WE_29") (pintype "input"))
      (node (ref "U7") (pin "29") (pinfunction "/WE_29") (pintype "input"))
    )
    (net (code "50") (name "WRITELO") (class "Default")
      (node (ref "U2") (pin "29") (pinfunction "/WE_29") (pintype "input"))
      (node (ref "U4") (pin "29") (pinfunction "/WE_29") (pintype "input"))
      (node (ref "U6") (pin "29") (pinfunction "/WE_29") (pintype "input"))
      (node (ref "U8") (pin "29") (pinfunction "/WE_29") (pintype "input"))
    )
    (net (code "51") (name "unconnected-(U$1-3.3V-Pad3V3)") (class "Default")
      (node (ref "U$1") (pin "3V3") (pinfunction "3.3V_3V3") (pintype "bidirectional"))
    )
    (net (code "52") (name "unconnected-(U$1-Pad-12V)") (class "Default")
      (node (ref "U$1") (pin "-12V") (pinfunction "-12V_-12V") (pintype "bidirectional"))
    )
    (net (code "53") (name "unconnected-(U$1-Pad5VSB)") (class "Default")
      (node (ref "U$1") (pin "5VSB") (pinfunction "5VSB_5VSB") (pintype "bidirectional"))
    )
    (net (code "54") (name "unconnected-(U$1-Pad12V)") (class "Default")
      (node (ref "U$1") (pin "12V") (pinfunction "12V_12V") (pintype "bidirectional"))
    )
    (net (code "55") (name "unconnected-(U$1-PadA19)") (class "Default")
      (node (ref "U$1") (pin "A19") (pinfunction "A19_A19") (pintype "bidirectional"))
    )
    (net (code "56") (name "unconnected-(U$1-PadA22)") (class "Default")
      (node (ref "U$1") (pin "A22") (pinfunction "A22_A22") (pintype "bidirectional"))
    )
    (net (code "57") (name "unconnected-(U$1-PadA23)") (class "Default")
      (node (ref "U$1") (pin "A23") (pinfunction "A23_A23") (pintype "bidirectional"))
    )
    (net (code "58") (name "unconnected-(U$1-PadCLK)") (class "Default")
      (node (ref "U$1") (pin "CLK") (pinfunction "CLK_CLK") (pintype "bidirectional"))
    )
    (net (code "59") (name "unconnected-(U$1-PadE)") (class "Default")
      (node (ref "U$1") (pin "E") (pinfunction "E_E") (pintype "bidirectional"))
    )
    (net (code "60") (name "unconnected-(U$1-PadVPA)") (class "Default")
      (node (ref "U$1") (pin "VPA") (pinfunction "VPA_VPA") (pintype "bidirectional"))
    )
    (net (code "61") (name "unconnected-(U$1-Pad{slash}CLK)") (class "Default")
      (node (ref "U$1") (pin "/CLK") (pinfunction "/CLK_/CLK") (pintype "bidirectional"))
    )
    (net (code "62") (name "unconnected-(U$1-Pad{slash}RESET)") (class "Default")
      (node (ref "U$1") (pin "/RESET") (pinfunction "/RESET_/RESET") (pintype "bidirectional"))
    )
    (net (code "63") (name "unconnected-(U$1-Pad{slash}VMA)") (class "Default")
      (node (ref "U$1") (pin "/VMA") (pinfunction "/VMA_/VMA") (pintype "bidirectional"))
    )
    (net (code "64") (name "{slash}AS") (class "Default")
      (node (ref "U$1") (pin "/AS") (pinfunction "/AS_/AS") (pintype "bidirectional"))
    )
    (net (code "65") (name "{slash}LDS") (class "Default")
      (node (ref "U$1") (pin "/LDS") (pinfunction "/LDS_/LDS") (pintype "bidirectional"))
    )
    (net (code "66") (name "{slash}UDS") (class "Default")
      (node (ref "U$1") (pin "/UDS") (pinfunction "/UDS_/UDS") (pintype "bidirectional"))
    )
  )
)
